# Dash7Duino.net
KiCad netlist of a schematic drawn in EAGLE
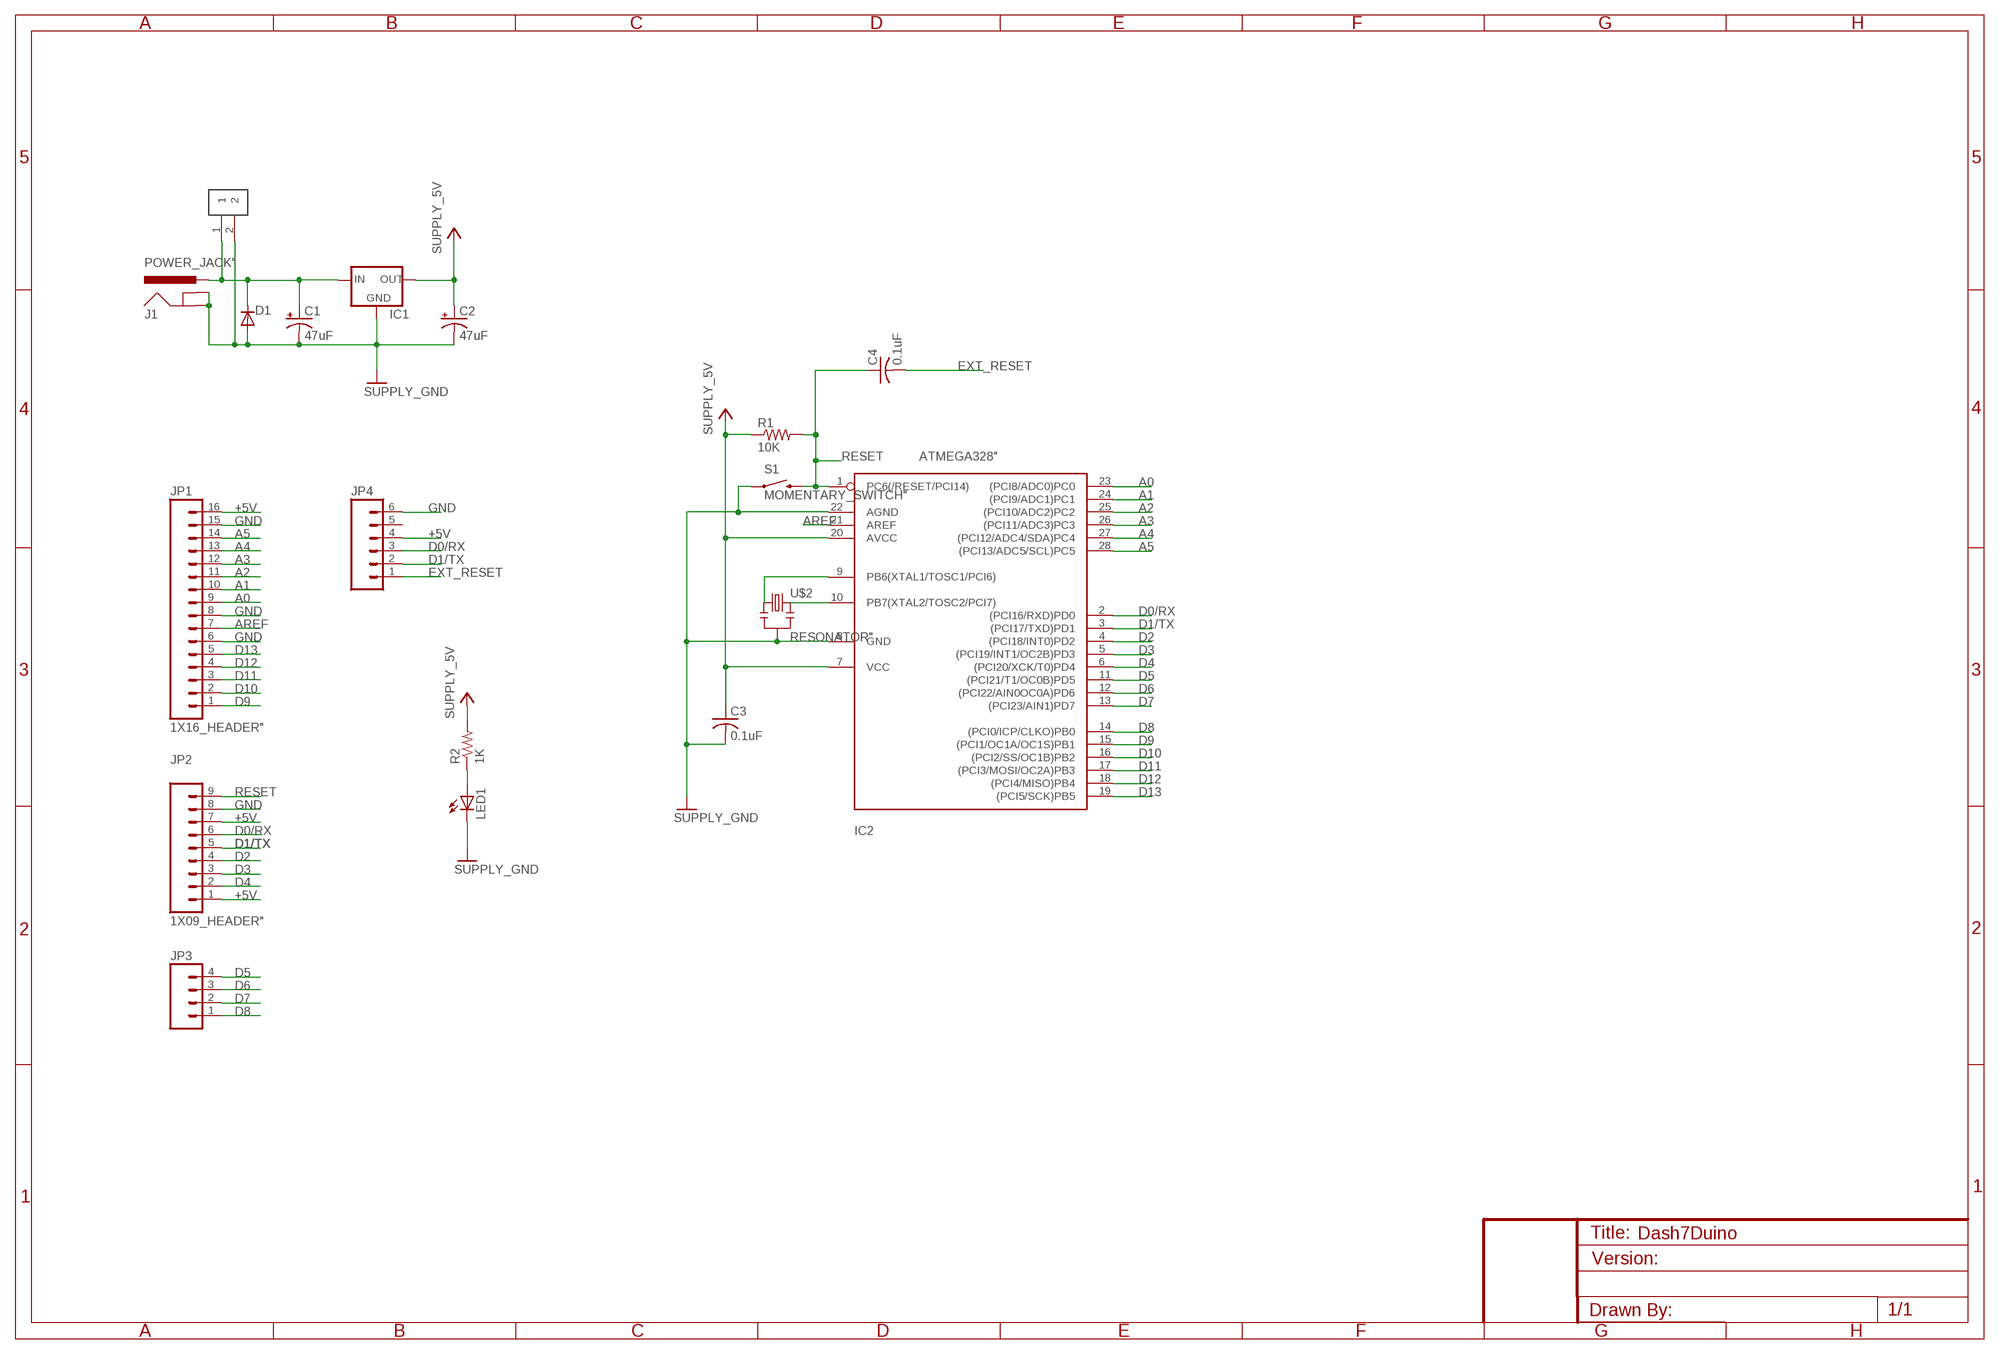
[diagram p0: schematic, sheet 1]

(export (version "E")
  (design (tool "Eeschema 10.0.6"))
  (components
    (comp (ref "C1")
      (value "47uF")
      (footprint "eagle-import:ELECTROLYTIC_CAP")
      (libsource (lib "eagle-import") (part "ELECTROLYTIC_CAP2.54MM"))
    )
    (comp (ref "C2")
      (value "47uF")
      (footprint "eagle-import:ELECTROLYTIC_CAP")
      (libsource (lib "eagle-import") (part "ELECTROLYTIC_CAP2.54MM"))
    )
    (comp (ref "C3")
      (value "0.1uF")
      (footprint "eagle-import:UNPOLARIZED_CAP")
      (libsource (lib "eagle-import") (part "UNPOLARIZED_CAP{dblquote}"))
    )
    (comp (ref "C4")
      (value "0.1uF")
      (footprint "eagle-import:UNPOLARIZED_CAP")
      (libsource (lib "eagle-import") (part "UNPOLARIZED_CAP{dblquote}"))
    )
    (comp (ref "D1")
      (value "DIODE")
      (footprint "eagle-import:DIODE-1N4001-KIT")
      (libsource (lib "eagle-import") (part "DIODE"))
    )
    (comp (ref "IC1")
      (value "REGULATOR")
      (footprint "eagle-import:L4931_REGULATOR")
      (libsource (lib "eagle-import") (part "REGULATOR"))
    )
    (comp (ref "IC2")
      (value "ATMEGA328\"")
      (footprint "eagle-import:ATMEGA328")
      (libsource (lib "eagle-import") (part "ATMEGA328{dblquote}"))
    )
    (comp (ref "J1")
      (value "POWER_JACK\"")
      (footprint "eagle-import:POWER_JACK")
      (libsource (lib "eagle-import") (part "POWER_JACK{dblquote}"))
    )
    (comp (ref "JP1")
      (value "1X16_HEADER\"")
      (footprint "eagle-import:1X16_HEADER")
      (libsource (lib "eagle-import") (part "1X16_HEADER{dblquote}"))
    )
    (comp (ref "JP2")
      (value "1X09_HEADER\"")
      (footprint "eagle-import:1X09_HEADER")
      (libsource (lib "eagle-import") (part "1X09_HEADER{dblquote}"))
    )
    (comp (ref "JP3")
      (value "1X04_HEADER\"")
      (footprint "eagle-import:1X04_HEADER")
      (libsource (lib "eagle-import") (part "1X04_HEADER{dblquote}"))
    )
    (comp (ref "JP4")
      (value "1X06_HEADER\"")
      (footprint "eagle-import:1X06_HEADER")
      (libsource (lib "eagle-import") (part "1X06_HEADER{dblquote}"))
    )
    (comp (ref "LED1")
      (value "LED3MM")
      (footprint "eagle-import:LED")
      (libsource (lib "eagle-import") (part "LED3MM"))
    )
    (comp (ref "R1")
      (value "10K")
      (footprint "eagle-import:RESISTOR")
      (libsource (lib "eagle-import") (part "RESISTOR1/6WATT"))
    )
    (comp (ref "R2")
      (value "1K")
      (footprint "eagle-import:RESISTOR")
      (libsource (lib "eagle-import") (part "RESISTOR1/6WATT"))
    )
    (comp (ref "S1")
      (value "MOMENTARY_SWITCH\"")
      (footprint "eagle-import:MOMENTARY_SWITCH")
      (libsource (lib "eagle-import") (part "MOMENTARY_SWITCH{dblquote}"))
    )
    (comp (ref "U$1")
      (value "1X02_HEADER")
      (footprint "eagle-import:1X02_HEADER")
      (libsource (lib "eagle-import") (part "1X02_HEADER"))
    )
    (comp (ref "U$2")
      (value "RESONATOR\"")
      (footprint "eagle-import:RESONATOR")
      (libsource (lib "eagle-import") (part "RESONATOR{dblquote}"))
    )
  )
  (nets
    (net (code "1") (name "/A0") (class "Default")
      (node (ref "IC2") (pin "23") (pinfunction "(PCI8/ADC0)PC0_23") (pintype "bidirectional"))
      (node (ref "JP1") (pin "9") (pinfunction "9_9") (pintype "passive"))
    )
    (net (code "2") (name "/A1") (class "Default")
      (node (ref "IC2") (pin "24") (pinfunction "(PCI9/ADC1)PC1_24") (pintype "bidirectional"))
      (node (ref "JP1") (pin "10") (pinfunction "10_10") (pintype "passive"))
    )
    (net (code "3") (name "/A2") (class "Default")
      (node (ref "IC2") (pin "25") (pinfunction "(PCI10/ADC2)PC2_25") (pintype "bidirectional"))
      (node (ref "JP1") (pin "11") (pinfunction "11_11") (pintype "passive"))
    )
    (net (code "4") (name "/A3") (class "Default")
      (node (ref "IC2") (pin "26") (pinfunction "(PCI11/ADC3)PC3_26") (pintype "bidirectional"))
      (node (ref "JP1") (pin "12") (pinfunction "12_12") (pintype "passive"))
    )
    (net (code "5") (name "/A4") (class "Default")
      (node (ref "IC2") (pin "27") (pinfunction "(PCI12/ADC4/SDA)PC4_27") (pintype "bidirectional"))
      (node (ref "JP1") (pin "13") (pinfunction "13_13") (pintype "passive"))
    )
    (net (code "6") (name "/A5") (class "Default")
      (node (ref "IC2") (pin "28") (pinfunction "(PCI13/ADC5/SCL)PC5_28") (pintype "bidirectional"))
      (node (ref "JP1") (pin "14") (pinfunction "14_14") (pintype "passive"))
    )
    (net (code "7") (name "/AREF") (class "Default")
      (node (ref "IC2") (pin "21") (pinfunction "AREF_21") (pintype "bidirectional"))
      (node (ref "JP1") (pin "7") (pinfunction "7_7") (pintype "passive"))
    )
    (net (code "8") (name "/D0{slash}RX") (class "Default")
      (node (ref "IC2") (pin "2") (pinfunction "(PCI16/RXD)PD0_2") (pintype "bidirectional"))
      (node (ref "JP2") (pin "6") (pinfunction "6_6") (pintype "passive"))
      (node (ref "JP4") (pin "3") (pinfunction "3_3") (pintype "passive"))
    )
    (net (code "9") (name "/D1{slash}TX") (class "Default")
      (node (ref "IC2") (pin "3") (pinfunction "(PCI17/TXD)PD1_3") (pintype "bidirectional"))
      (node (ref "JP2") (pin "5") (pinfunction "5_5") (pintype "passive"))
      (node (ref "JP4") (pin "2") (pinfunction "2_2") (pintype "passive"))
    )
    (net (code "10") (name "/D2") (class "Default")
      (node (ref "IC2") (pin "4") (pinfunction "(PCI18/INT0)PD2_4") (pintype "bidirectional"))
      (node (ref "JP2") (pin "4") (pinfunction "4_4") (pintype "passive"))
    )
    (net (code "11") (name "/D3") (class "Default")
      (node (ref "IC2") (pin "5") (pinfunction "(PCI19/INT1/OC2B)PD3_5") (pintype "bidirectional"))
      (node (ref "JP2") (pin "3") (pinfunction "3_3") (pintype "passive"))
    )
    (net (code "12") (name "/D4") (class "Default")
      (node (ref "IC2") (pin "6") (pinfunction "(PCI20/XCK/T0)PD4_6") (pintype "bidirectional"))
      (node (ref "JP2") (pin "2") (pinfunction "2_2") (pintype "passive"))
    )
    (net (code "13") (name "/D5") (class "Default")
      (node (ref "IC2") (pin "11") (pinfunction "(PCI21/T1/OC0B)PD5_11") (pintype "bidirectional"))
      (node (ref "JP3") (pin "4") (pinfunction "4_4") (pintype "passive"))
    )
    (net (code "14") (name "/D6") (class "Default")
      (node (ref "IC2") (pin "12") (pinfunction "(PCI22/AIN0OC0A)PD6_12") (pintype "bidirectional"))
      (node (ref "JP3") (pin "3") (pinfunction "3_3") (pintype "passive"))
    )
    (net (code "15") (name "/D7") (class "Default")
      (node (ref "IC2") (pin "13") (pinfunction "(PCI23/AIN1)PD7_13") (pintype "bidirectional"))
      (node (ref "JP3") (pin "2") (pinfunction "2_2") (pintype "passive"))
    )
    (net (code "16") (name "/D8") (class "Default")
      (node (ref "IC2") (pin "14") (pinfunction "(PCI0/ICP/CLKO)PB0_14") (pintype "bidirectional"))
      (node (ref "JP3") (pin "1") (pinfunction "1_1") (pintype "passive"))
    )
    (net (code "17") (name "/D9") (class "Default")
      (node (ref "IC2") (pin "15") (pinfunction "(PCI1/OC1A/OC1S)PB1_15") (pintype "bidirectional"))
      (node (ref "JP1") (pin "1") (pinfunction "1_1") (pintype "passive"))
    )
    (net (code "18") (name "/D10") (class "Default")
      (node (ref "IC2") (pin "16") (pinfunction "(PCI2/SS/OC1B)PB2_16") (pintype "bidirectional"))
      (node (ref "JP1") (pin "2") (pinfunction "2_2") (pintype "passive"))
    )
    (net (code "19") (name "/D11") (class "Default")
      (node (ref "IC2") (pin "17") (pinfunction "(PCI3/MOSI/OC2A)PB3_17") (pintype "bidirectional"))
      (node (ref "JP1") (pin "3") (pinfunction "3_3") (pintype "passive"))
    )
    (net (code "20") (name "/D12") (class "Default")
      (node (ref "IC2") (pin "18") (pinfunction "(PCI4/MISO)PB4_18") (pintype "bidirectional"))
      (node (ref "JP1") (pin "4") (pinfunction "4_4") (pintype "passive"))
    )
    (net (code "21") (name "/D13") (class "Default")
      (node (ref "IC2") (pin "19") (pinfunction "(PCI5/SCK)PB5_19") (pintype "bidirectional"))
      (node (ref "JP1") (pin "5") (pinfunction "5_5") (pintype "passive"))
    )
    (net (code "22") (name "/EXT_RESET") (class "Default")
      (node (ref "C4") (pin "2") (pinfunction "2_2") (pintype "passive"))
      (node (ref "JP4") (pin "1") (pinfunction "1_1") (pintype "passive"))
    )
    (net (code "23") (name "/RESET") (class "Default")
      (node (ref "C4") (pin "1") (pinfunction "1_1") (pintype "passive"))
      (node (ref "IC2") (pin "1") (pinfunction "PC6(/RESET/PCI14)_1") (pintype "bidirectional"))
      (node (ref "JP2") (pin "9") (pinfunction "9_9") (pintype "passive"))
      (node (ref "R1") (pin "2") (pinfunction "2_2") (pintype "passive"))
      (node (ref "S1") (pin "3") (pinfunction "2_3") (pintype "passive"))
    )
    (net (code "24") (name "Net-(C1-Pad+)") (class "Default")
      (node (ref "C1") (pin "+") (pinfunction "+_+") (pintype "passive"))
      (node (ref "D1") (pin "C") (pinfunction "C_C") (pintype "passive"))
      (node (ref "IC1") (pin "IN") (pinfunction "IN_IN") (pintype "input"))
      (node (ref "J1") (pin "PWR") (pinfunction "PWR_PWR") (pintype "bidirectional"))
      (node (ref "U$1") (pin "1") (pinfunction "1_1") (pintype "bidirectional"))
    )
    (net (code "25") (name "Net-(IC2-PB6(XTAL1{slash}TOSC1{slash}PCI6))") (class "Default")
      (node (ref "IC2") (pin "9") (pinfunction "PB6(XTAL1/TOSC1/PCI6)_9") (pintype "bidirectional"))
      (node (ref "U$2") (pin "1") (pinfunction "1_1") (pintype "passive"))
    )
    (net (code "26") (name "Net-(IC2-PB7(XTAL2{slash}TOSC2{slash}PCI7))") (class "Default")
      (node (ref "IC2") (pin "10") (pinfunction "PB7(XTAL2/TOSC2/PCI7)_10") (pintype "bidirectional"))
      (node (ref "U$2") (pin "3") (pinfunction "3_3") (pintype "passive"))
    )
    (net (code "27") (name "Net-(LED1-PadA)") (class "Default")
      (node (ref "LED1") (pin "A") (pinfunction "A_A") (pintype "passive"))
      (node (ref "R2") (pin "1") (pinfunction "1_1") (pintype "passive"))
    )
    (net (code "28") (name "SUPPLY_5V") (class "Default")
      (node (ref "C2") (pin "+") (pinfunction "+_+") (pintype "passive"))
      (node (ref "C3") (pin "1") (pinfunction "1_1") (pintype "passive"))
      (node (ref "IC1") (pin "OUT") (pinfunction "OUT_OUT") (pintype "passive"))
      (node (ref "IC2") (pin "20") (pinfunction "AVCC_20") (pintype "bidirectional"))
      (node (ref "IC2") (pin "7") (pinfunction "VCC_7") (pintype "bidirectional"))
      (node (ref "JP1") (pin "16") (pinfunction "16_16") (pintype "passive"))
      (node (ref "JP2") (pin "1") (pinfunction "1_1") (pintype "passive"))
      (node (ref "JP2") (pin "7") (pinfunction "7_7") (pintype "passive"))
      (node (ref "JP4") (pin "4") (pinfunction "4_4") (pintype "passive"))
      (node (ref "R1") (pin "1") (pinfunction "1_1") (pintype "passive"))
      (node (ref "R2") (pin "2") (pinfunction "2_2") (pintype "passive"))
    )
    (net (code "29") (name "SUPPLY_GND") (class "Default")
      (node (ref "C1") (pin "-") (pinfunction "-_-") (pintype "passive"))
      (node (ref "C2") (pin "-") (pinfunction "-_-") (pintype "passive"))
      (node (ref "C3") (pin "2") (pinfunction "2_2") (pintype "passive"))
      (node (ref "D1") (pin "A") (pinfunction "A_A") (pintype "passive"))
      (node (ref "IC1") (pin "GND") (pinfunction "GND_GND") (pintype "input"))
      (node (ref "IC2") (pin "22") (pinfunction "AGND_22") (pintype "bidirectional"))
      (node (ref "IC2") (pin "8") (pinfunction "GND_8") (pintype "bidirectional"))
      (node (ref "J1") (pin "GND") (pinfunction "GND_GND") (pintype "bidirectional"))
      (node (ref "J1") (pin "GNDBREAK") (pinfunction "GNDBREAK_GNDBREAK") (pintype "bidirectional"))
      (node (ref "JP1") (pin "15") (pinfunction "15_15") (pintype "passive"))
      (node (ref "JP1") (pin "6") (pinfunction "6_6") (pintype "passive"))
      (node (ref "JP1") (pin "8") (pinfunction "8_8") (pintype "passive"))
      (node (ref "JP2") (pin "8") (pinfunction "8_8") (pintype "passive"))
      (node (ref "JP4") (pin "6") (pinfunction "6_6") (pintype "passive"))
      (node (ref "LED1") (pin "K") (pinfunction "C_K") (pintype "passive"))
      (node (ref "S1") (pin "1") (pinfunction "1_1") (pintype "passive"))
      (node (ref "U$1") (pin "2") (pinfunction "2_2") (pintype "bidirectional"))
      (node (ref "U$2") (pin "2") (pinfunction "2_2") (pintype "passive"))
    )
    (net (code "30") (name "unconnected-(JP4-Pad5)") (class "Default")
      (node (ref "JP4") (pin "5") (pinfunction "5_5") (pintype "passive"))
    )
  )
)
